# PCB_PressureSensitiveConverterBoard.net
KiCad netlist of a schematic drawn in EasyEDA Pro
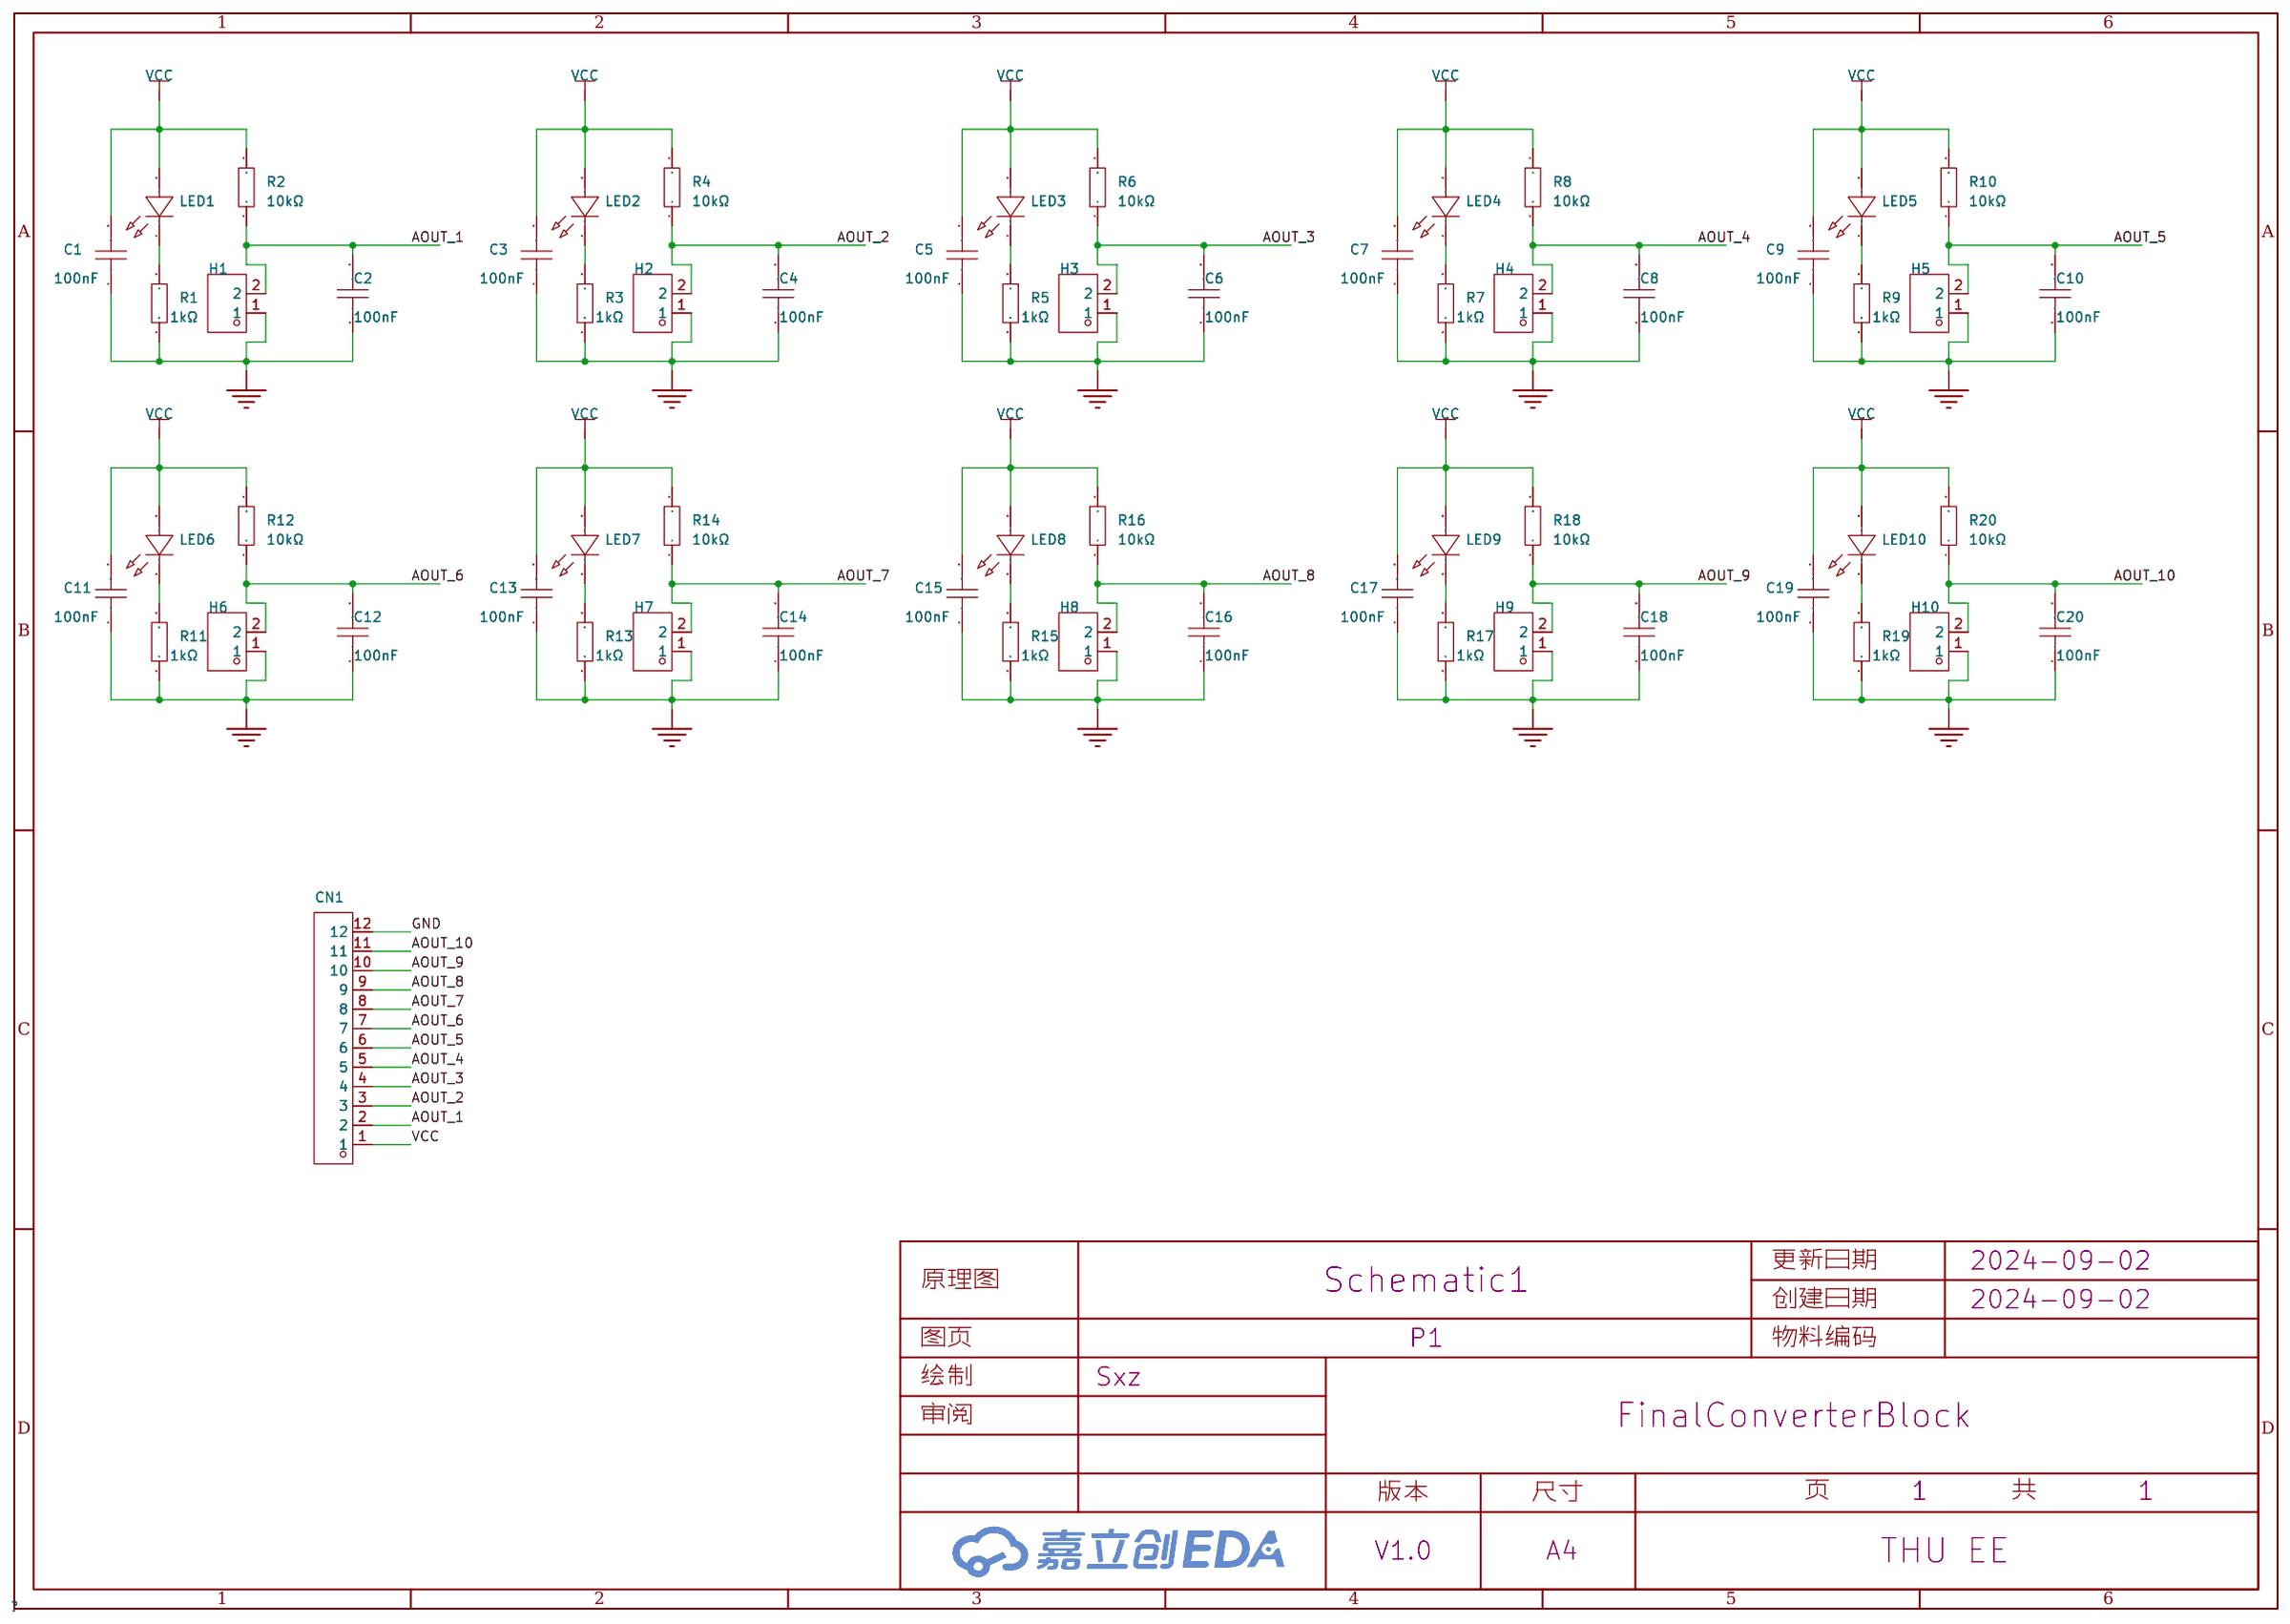
[diagram p0: schematic sheet]

(export (version "E")
  (design (tool "Eeschema 10.0.6"))
  (components
    (comp (ref "C1")
      (value "100nF")
      (footprint "easyedapro:C0603")
      (description "容值:100nF;精度:±10%;额定电压:50V;材质(温度系数):X7R;")
      (fields
        (field (name "Manufacturer Part") "CC0603KRX7R9BB104")
        (field (name "Manufacturer") "YAGEO(国巨)")
      )
      (libsource (lib "easyedapro") (part "CC0603KRX7R9BB104"))
    )
    (comp (ref "C2")
      (value "100nF")
      (footprint "easyedapro:C0603")
      (description "容值:100nF;精度:±10%;额定电压:50V;材质(温度系数):X7R;")
      (fields
        (field (name "Manufacturer Part") "CC0603KRX7R9BB104")
        (field (name "Manufacturer") "YAGEO(国巨)")
      )
      (libsource (lib "easyedapro") (part "CC0603KRX7R9BB104"))
    )
    (comp (ref "C3")
      (value "100nF")
      (footprint "easyedapro:C0603")
      (description "容值:100nF;精度:±10%;额定电压:50V;材质(温度系数):X7R;")
      (fields
        (field (name "Manufacturer Part") "CC0603KRX7R9BB104")
        (field (name "Manufacturer") "YAGEO(国巨)")
      )
      (libsource (lib "easyedapro") (part "CC0603KRX7R9BB104"))
    )
    (comp (ref "C4")
      (value "100nF")
      (footprint "easyedapro:C0603")
      (description "容值:100nF;精度:±10%;额定电压:50V;材质(温度系数):X7R;")
      (fields
        (field (name "Manufacturer Part") "CC0603KRX7R9BB104")
        (field (name "Manufacturer") "YAGEO(国巨)")
      )
      (libsource (lib "easyedapro") (part "CC0603KRX7R9BB104"))
    )
    (comp (ref "C5")
      (value "100nF")
      (footprint "easyedapro:C0603")
      (description "容值:100nF;精度:±10%;额定电压:50V;材质(温度系数):X7R;")
      (fields
        (field (name "Manufacturer Part") "CC0603KRX7R9BB104")
        (field (name "Manufacturer") "YAGEO(国巨)")
      )
      (libsource (lib "easyedapro") (part "CC0603KRX7R9BB104"))
    )
    (comp (ref "C6")
      (value "100nF")
      (footprint "easyedapro:C0603")
      (description "容值:100nF;精度:±10%;额定电压:50V;材质(温度系数):X7R;")
      (fields
        (field (name "Manufacturer Part") "CC0603KRX7R9BB104")
        (field (name "Manufacturer") "YAGEO(国巨)")
      )
      (libsource (lib "easyedapro") (part "CC0603KRX7R9BB104"))
    )
    (comp (ref "C7")
      (value "100nF")
      (footprint "easyedapro:C0603")
      (description "容值:100nF;精度:±10%;额定电压:50V;材质(温度系数):X7R;")
      (fields
        (field (name "Manufacturer Part") "CC0603KRX7R9BB104")
        (field (name "Manufacturer") "YAGEO(国巨)")
      )
      (libsource (lib "easyedapro") (part "CC0603KRX7R9BB104"))
    )
    (comp (ref "C8")
      (value "100nF")
      (footprint "easyedapro:C0603")
      (description "容值:100nF;精度:±10%;额定电压:50V;材质(温度系数):X7R;")
      (fields
        (field (name "Manufacturer Part") "CC0603KRX7R9BB104")
        (field (name "Manufacturer") "YAGEO(国巨)")
      )
      (libsource (lib "easyedapro") (part "CC0603KRX7R9BB104"))
    )
    (comp (ref "C9")
      (value "100nF")
      (footprint "easyedapro:C0603")
      (description "容值:100nF;精度:±10%;额定电压:50V;材质(温度系数):X7R;")
      (fields
        (field (name "Manufacturer Part") "CC0603KRX7R9BB104")
        (field (name "Manufacturer") "YAGEO(国巨)")
      )
      (libsource (lib "easyedapro") (part "CC0603KRX7R9BB104"))
    )
    (comp (ref "C10")
      (value "100nF")
      (footprint "easyedapro:C0603")
      (description "容值:100nF;精度:±10%;额定电压:50V;材质(温度系数):X7R;")
      (fields
        (field (name "Manufacturer Part") "CC0603KRX7R9BB104")
        (field (name "Manufacturer") "YAGEO(国巨)")
      )
      (libsource (lib "easyedapro") (part "CC0603KRX7R9BB104"))
    )
    (comp (ref "C11")
      (value "100nF")
      (footprint "easyedapro:C0603")
      (description "容值:100nF;精度:±10%;额定电压:50V;材质(温度系数):X7R;")
      (fields
        (field (name "Manufacturer Part") "CC0603KRX7R9BB104")
        (field (name "Manufacturer") "YAGEO(国巨)")
      )
      (libsource (lib "easyedapro") (part "CC0603KRX7R9BB104"))
    )
    (comp (ref "C12")
      (value "100nF")
      (footprint "easyedapro:C0603")
      (description "容值:100nF;精度:±10%;额定电压:50V;材质(温度系数):X7R;")
      (fields
        (field (name "Manufacturer Part") "CC0603KRX7R9BB104")
        (field (name "Manufacturer") "YAGEO(国巨)")
      )
      (libsource (lib "easyedapro") (part "CC0603KRX7R9BB104"))
    )
    (comp (ref "C13")
      (value "100nF")
      (footprint "easyedapro:C0603")
      (description "容值:100nF;精度:±10%;额定电压:50V;材质(温度系数):X7R;")
      (fields
        (field (name "Manufacturer Part") "CC0603KRX7R9BB104")
        (field (name "Manufacturer") "YAGEO(国巨)")
      )
      (libsource (lib "easyedapro") (part "CC0603KRX7R9BB104"))
    )
    (comp (ref "C14")
      (value "100nF")
      (footprint "easyedapro:C0603")
      (description "容值:100nF;精度:±10%;额定电压:50V;材质(温度系数):X7R;")
      (fields
        (field (name "Manufacturer Part") "CC0603KRX7R9BB104")
        (field (name "Manufacturer") "YAGEO(国巨)")
      )
      (libsource (lib "easyedapro") (part "CC0603KRX7R9BB104"))
    )
    (comp (ref "C15")
      (value "100nF")
      (footprint "easyedapro:C0603")
      (description "容值:100nF;精度:±10%;额定电压:50V;材质(温度系数):X7R;")
      (fields
        (field (name "Manufacturer Part") "CC0603KRX7R9BB104")
        (field (name "Manufacturer") "YAGEO(国巨)")
      )
      (libsource (lib "easyedapro") (part "CC0603KRX7R9BB104"))
    )
    (comp (ref "C16")
      (value "100nF")
      (footprint "easyedapro:C0603")
      (description "容值:100nF;精度:±10%;额定电压:50V;材质(温度系数):X7R;")
      (fields
        (field (name "Manufacturer Part") "CC0603KRX7R9BB104")
        (field (name "Manufacturer") "YAGEO(国巨)")
      )
      (libsource (lib "easyedapro") (part "CC0603KRX7R9BB104"))
    )
    (comp (ref "C17")
      (value "100nF")
      (footprint "easyedapro:C0603")
      (description "容值:100nF;精度:±10%;额定电压:50V;材质(温度系数):X7R;")
      (fields
        (field (name "Manufacturer Part") "CC0603KRX7R9BB104")
        (field (name "Manufacturer") "YAGEO(国巨)")
      )
      (libsource (lib "easyedapro") (part "CC0603KRX7R9BB104"))
    )
    (comp (ref "C18")
      (value "100nF")
      (footprint "easyedapro:C0603")
      (description "容值:100nF;精度:±10%;额定电压:50V;材质(温度系数):X7R;")
      (fields
        (field (name "Manufacturer Part") "CC0603KRX7R9BB104")
        (field (name "Manufacturer") "YAGEO(国巨)")
      )
      (libsource (lib "easyedapro") (part "CC0603KRX7R9BB104"))
    )
    (comp (ref "C19")
      (value "100nF")
      (footprint "easyedapro:C0603")
      (description "容值:100nF;精度:±10%;额定电压:50V;材质(温度系数):X7R;")
      (fields
        (field (name "Manufacturer Part") "CC0603KRX7R9BB104")
        (field (name "Manufacturer") "YAGEO(国巨)")
      )
      (libsource (lib "easyedapro") (part "CC0603KRX7R9BB104"))
    )
    (comp (ref "C20")
      (value "100nF")
      (footprint "easyedapro:C0603")
      (description "容值:100nF;精度:±10%;额定电压:50V;材质(温度系数):X7R;")
      (fields
        (field (name "Manufacturer Part") "CC0603KRX7R9BB104")
        (field (name "Manufacturer") "YAGEO(国巨)")
      )
      (libsource (lib "easyedapro") (part "CC0603KRX7R9BB104"))
    )
    (comp (ref "CN1")
      (value "HB-PH3-254112PB2GOP")
      (footprint "easyedapro:HDR-TH_12P-P2.54-V-M")
      (fields (field (name "Manufacturer") "HANBO(汉博)"))
      (libsource (lib "easyedapro") (part "HB-PH3-254112PB2GOP"))
    )
    (comp (ref "H1")
      (value "PZ254V-11-02P")
      (footprint "easyedapro:HDR-TH_2P-P2.54-V-M")
      (fields (field (name "Manufacturer") "XFCN(兴飞)"))
      (libsource (lib "easyedapro") (part "PZ254V-11-02P"))
    )
    (comp (ref "H2")
      (value "PZ254V-11-02P")
      (footprint "easyedapro:HDR-TH_2P-P2.54-V-M")
      (fields (field (name "Manufacturer") "XFCN(兴飞)"))
      (libsource (lib "easyedapro") (part "PZ254V-11-02P"))
    )
    (comp (ref "H3")
      (value "PZ254V-11-02P")
      (footprint "easyedapro:HDR-TH_2P-P2.54-V-M")
      (fields (field (name "Manufacturer") "XFCN(兴飞)"))
      (libsource (lib "easyedapro") (part "PZ254V-11-02P"))
    )
    (comp (ref "H4")
      (value "PZ254V-11-02P")
      (footprint "easyedapro:HDR-TH_2P-P2.54-V-M")
      (fields (field (name "Manufacturer") "XFCN(兴飞)"))
      (libsource (lib "easyedapro") (part "PZ254V-11-02P"))
    )
    (comp (ref "H5")
      (value "PZ254V-11-02P")
      (footprint "easyedapro:HDR-TH_2P-P2.54-V-M")
      (fields (field (name "Manufacturer") "XFCN(兴飞)"))
      (libsource (lib "easyedapro") (part "PZ254V-11-02P"))
    )
    (comp (ref "H6")
      (value "PZ254V-11-02P")
      (footprint "easyedapro:HDR-TH_2P-P2.54-V-M")
      (fields (field (name "Manufacturer") "XFCN(兴飞)"))
      (libsource (lib "easyedapro") (part "PZ254V-11-02P"))
    )
    (comp (ref "H7")
      (value "PZ254V-11-02P")
      (footprint "easyedapro:HDR-TH_2P-P2.54-V-M")
      (fields (field (name "Manufacturer") "XFCN(兴飞)"))
      (libsource (lib "easyedapro") (part "PZ254V-11-02P"))
    )
    (comp (ref "H8")
      (value "PZ254V-11-02P")
      (footprint "easyedapro:HDR-TH_2P-P2.54-V-M")
      (fields (field (name "Manufacturer") "XFCN(兴飞)"))
      (libsource (lib "easyedapro") (part "PZ254V-11-02P"))
    )
    (comp (ref "H9")
      (value "PZ254V-11-02P")
      (footprint "easyedapro:HDR-TH_2P-P2.54-V-M")
      (fields (field (name "Manufacturer") "XFCN(兴飞)"))
      (libsource (lib "easyedapro") (part "PZ254V-11-02P"))
    )
    (comp (ref "H10")
      (value "PZ254V-11-02P")
      (footprint "easyedapro:HDR-TH_2P-P2.54-V-M")
      (fields (field (name "Manufacturer") "XFCN(兴飞)"))
      (libsource (lib "easyedapro") (part "PZ254V-11-02P"))
    )
    (comp (ref "LED1")
      (value "XL-1608SURC-06")
      (footprint "easyedapro:LED0603-RD_RED")
      (description "发光颜色:红色;功率:55mW;正向电流:25mA;主波长:617nm~621nm;透镜颜色:无色透明透镜;色温:-;发光角度:120°;载带方式:正贴;工作温度:-30°C~+85°C;")
      (fields (field (name "Manufacturer") "XINGLIGHT(成兴光)"))
      (libsource (lib "easyedapro") (part "XL-1608SURC-06"))
    )
    (comp (ref "LED2")
      (value "XL-1608SURC-06")
      (footprint "easyedapro:LED0603-RD_RED")
      (description "发光颜色:红色;功率:55mW;正向电流:25mA;主波长:617nm~621nm;透镜颜色:无色透明透镜;色温:-;发光角度:120°;载带方式:正贴;工作温度:-30°C~+85°C;")
      (fields (field (name "Manufacturer") "XINGLIGHT(成兴光)"))
      (libsource (lib "easyedapro") (part "XL-1608SURC-06"))
    )
    (comp (ref "LED3")
      (value "XL-1608SURC-06")
      (footprint "easyedapro:LED0603-RD_RED")
      (description "发光颜色:红色;功率:55mW;正向电流:25mA;主波长:617nm~621nm;透镜颜色:无色透明透镜;色温:-;发光角度:120°;载带方式:正贴;工作温度:-30°C~+85°C;")
      (fields (field (name "Manufacturer") "XINGLIGHT(成兴光)"))
      (libsource (lib "easyedapro") (part "XL-1608SURC-06"))
    )
    (comp (ref "LED4")
      (value "XL-1608SURC-06")
      (footprint "easyedapro:LED0603-RD_RED")
      (description "发光颜色:红色;功率:55mW;正向电流:25mA;主波长:617nm~621nm;透镜颜色:无色透明透镜;色温:-;发光角度:120°;载带方式:正贴;工作温度:-30°C~+85°C;")
      (fields (field (name "Manufacturer") "XINGLIGHT(成兴光)"))
      (libsource (lib "easyedapro") (part "XL-1608SURC-06"))
    )
    (comp (ref "LED5")
      (value "XL-1608SURC-06")
      (footprint "easyedapro:LED0603-RD_RED")
      (description "发光颜色:红色;功率:55mW;正向电流:25mA;主波长:617nm~621nm;透镜颜色:无色透明透镜;色温:-;发光角度:120°;载带方式:正贴;工作温度:-30°C~+85°C;")
      (fields (field (name "Manufacturer") "XINGLIGHT(成兴光)"))
      (libsource (lib "easyedapro") (part "XL-1608SURC-06"))
    )
    (comp (ref "LED6")
      (value "XL-1608SURC-06")
      (footprint "easyedapro:LED0603-RD_RED")
      (description "发光颜色:红色;功率:55mW;正向电流:25mA;主波长:617nm~621nm;透镜颜色:无色透明透镜;色温:-;发光角度:120°;载带方式:正贴;工作温度:-30°C~+85°C;")
      (fields (field (name "Manufacturer") "XINGLIGHT(成兴光)"))
      (libsource (lib "easyedapro") (part "XL-1608SURC-06"))
    )
    (comp (ref "LED7")
      (value "XL-1608SURC-06")
      (footprint "easyedapro:LED0603-RD_RED")
      (description "发光颜色:红色;功率:55mW;正向电流:25mA;主波长:617nm~621nm;透镜颜色:无色透明透镜;色温:-;发光角度:120°;载带方式:正贴;工作温度:-30°C~+85°C;")
      (fields (field (name "Manufacturer") "XINGLIGHT(成兴光)"))
      (libsource (lib "easyedapro") (part "XL-1608SURC-06"))
    )
    (comp (ref "LED8")
      (value "XL-1608SURC-06")
      (footprint "easyedapro:LED0603-RD_RED")
      (description "发光颜色:红色;功率:55mW;正向电流:25mA;主波长:617nm~621nm;透镜颜色:无色透明透镜;色温:-;发光角度:120°;载带方式:正贴;工作温度:-30°C~+85°C;")
      (fields (field (name "Manufacturer") "XINGLIGHT(成兴光)"))
      (libsource (lib "easyedapro") (part "XL-1608SURC-06"))
    )
    (comp (ref "LED9")
      (value "XL-1608SURC-06")
      (footprint "easyedapro:LED0603-RD_RED")
      (description "发光颜色:红色;功率:55mW;正向电流:25mA;主波长:617nm~621nm;透镜颜色:无色透明透镜;色温:-;发光角度:120°;载带方式:正贴;工作温度:-30°C~+85°C;")
      (fields (field (name "Manufacturer") "XINGLIGHT(成兴光)"))
      (libsource (lib "easyedapro") (part "XL-1608SURC-06"))
    )
    (comp (ref "LED10")
      (value "XL-1608SURC-06")
      (footprint "easyedapro:LED0603-RD_RED")
      (description "发光颜色:红色;功率:55mW;正向电流:25mA;主波长:617nm~621nm;透镜颜色:无色透明透镜;色温:-;发光角度:120°;载带方式:正贴;工作温度:-30°C~+85°C;")
      (fields (field (name "Manufacturer") "XINGLIGHT(成兴光)"))
      (libsource (lib "easyedapro") (part "XL-1608SURC-06"))
    )
    (comp (ref "R1")
      (value "1kΩ")
      (footprint "easyedapro:R0603")
      (description "电阻类型:厚膜电阻;阻值:1kΩ;精度:±1%;功率:100mW;最大工作电压:75V;温度系数:±100ppm/°C;")
      (fields
        (field (name "Manufacturer Part") "0603WAF1001T5E")
        (field (name "Manufacturer") "UNI-ROYAL(厚声)")
      )
      (libsource (lib "easyedapro") (part "0603WAF1001T5E"))
    )
    (comp (ref "R2")
      (value "10kΩ")
      (footprint "easyedapro:R0603")
      (description "电阻类型:厚膜电阻;阻值:10kΩ;精度:±1%;功率:100mW;最大工作电压:75V;温度系数:±100ppm/°C;")
      (fields
        (field (name "Manufacturer Part") "0603WAF1002T5E")
        (field (name "Manufacturer") "UNI-ROYAL(厚声)")
      )
      (libsource (lib "easyedapro") (part "0603WAF1002T5E"))
    )
    (comp (ref "R3")
      (value "1kΩ")
      (footprint "easyedapro:R0603")
      (description "电阻类型:厚膜电阻;阻值:1kΩ;精度:±1%;功率:100mW;最大工作电压:75V;温度系数:±100ppm/°C;")
      (fields
        (field (name "Manufacturer Part") "0603WAF1001T5E")
        (field (name "Manufacturer") "UNI-ROYAL(厚声)")
      )
      (libsource (lib "easyedapro") (part "0603WAF1001T5E"))
    )
    (comp (ref "R4")
      (value "10kΩ")
      (footprint "easyedapro:R0603")
      (description "电阻类型:厚膜电阻;阻值:10kΩ;精度:±1%;功率:100mW;最大工作电压:75V;温度系数:±100ppm/°C;")
      (fields
        (field (name "Manufacturer Part") "0603WAF1002T5E")
        (field (name "Manufacturer") "UNI-ROYAL(厚声)")
      )
      (libsource (lib "easyedapro") (part "0603WAF1002T5E"))
    )
    (comp (ref "R5")
      (value "1kΩ")
      (footprint "easyedapro:R0603")
      (description "电阻类型:厚膜电阻;阻值:1kΩ;精度:±1%;功率:100mW;最大工作电压:75V;温度系数:±100ppm/°C;")
      (fields
        (field (name "Manufacturer Part") "0603WAF1001T5E")
        (field (name "Manufacturer") "UNI-ROYAL(厚声)")
      )
      (libsource (lib "easyedapro") (part "0603WAF1001T5E"))
    )
    (comp (ref "R6")
      (value "10kΩ")
      (footprint "easyedapro:R0603")
      (description "电阻类型:厚膜电阻;阻值:10kΩ;精度:±1%;功率:100mW;最大工作电压:75V;温度系数:±100ppm/°C;")
      (fields
        (field (name "Manufacturer Part") "0603WAF1002T5E")
        (field (name "Manufacturer") "UNI-ROYAL(厚声)")
      )
      (libsource (lib "easyedapro") (part "0603WAF1002T5E"))
    )
    (comp (ref "R7")
      (value "1kΩ")
      (footprint "easyedapro:R0603")
      (description "电阻类型:厚膜电阻;阻值:1kΩ;精度:±1%;功率:100mW;最大工作电压:75V;温度系数:±100ppm/°C;")
      (fields
        (field (name "Manufacturer Part") "0603WAF1001T5E")
        (field (name "Manufacturer") "UNI-ROYAL(厚声)")
      )
      (libsource (lib "easyedapro") (part "0603WAF1001T5E"))
    )
    (comp (ref "R8")
      (value "10kΩ")
      (footprint "easyedapro:R0603")
      (description "电阻类型:厚膜电阻;阻值:10kΩ;精度:±1%;功率:100mW;最大工作电压:75V;温度系数:±100ppm/°C;")
      (fields
        (field (name "Manufacturer Part") "0603WAF1002T5E")
        (field (name "Manufacturer") "UNI-ROYAL(厚声)")
      )
      (libsource (lib "easyedapro") (part "0603WAF1002T5E"))
    )
    (comp (ref "R9")
      (value "1kΩ")
      (footprint "easyedapro:R0603")
      (description "电阻类型:厚膜电阻;阻值:1kΩ;精度:±1%;功率:100mW;最大工作电压:75V;温度系数:±100ppm/°C;")
      (fields
        (field (name "Manufacturer Part") "0603WAF1001T5E")
        (field (name "Manufacturer") "UNI-ROYAL(厚声)")
      )
      (libsource (lib "easyedapro") (part "0603WAF1001T5E"))
    )
    (comp (ref "R10")
      (value "10kΩ")
      (footprint "easyedapro:R0603")
      (description "电阻类型:厚膜电阻;阻值:10kΩ;精度:±1%;功率:100mW;最大工作电压:75V;温度系数:±100ppm/°C;")
      (fields
        (field (name "Manufacturer Part") "0603WAF1002T5E")
        (field (name "Manufacturer") "UNI-ROYAL(厚声)")
      )
      (libsource (lib "easyedapro") (part "0603WAF1002T5E"))
    )
    (comp (ref "R11")
      (value "1kΩ")
      (footprint "easyedapro:R0603")
      (description "电阻类型:厚膜电阻;阻值:1kΩ;精度:±1%;功率:100mW;最大工作电压:75V;温度系数:±100ppm/°C;")
      (fields
        (field (name "Manufacturer Part") "0603WAF1001T5E")
        (field (name "Manufacturer") "UNI-ROYAL(厚声)")
      )
      (libsource (lib "easyedapro") (part "0603WAF1001T5E"))
    )
    (comp (ref "R12")
      (value "10kΩ")
      (footprint "easyedapro:R0603")
      (description "电阻类型:厚膜电阻;阻值:10kΩ;精度:±1%;功率:100mW;最大工作电压:75V;温度系数:±100ppm/°C;")
      (fields
        (field (name "Manufacturer Part") "0603WAF1002T5E")
        (field (name "Manufacturer") "UNI-ROYAL(厚声)")
      )
      (libsource (lib "easyedapro") (part "0603WAF1002T5E"))
    )
    (comp (ref "R13")
      (value "1kΩ")
      (footprint "easyedapro:R0603")
      (description "电阻类型:厚膜电阻;阻值:1kΩ;精度:±1%;功率:100mW;最大工作电压:75V;温度系数:±100ppm/°C;")
      (fields
        (field (name "Manufacturer Part") "0603WAF1001T5E")
        (field (name "Manufacturer") "UNI-ROYAL(厚声)")
      )
      (libsource (lib "easyedapro") (part "0603WAF1001T5E"))
    )
    (comp (ref "R14")
      (value "10kΩ")
      (footprint "easyedapro:R0603")
      (description "电阻类型:厚膜电阻;阻值:10kΩ;精度:±1%;功率:100mW;最大工作电压:75V;温度系数:±100ppm/°C;")
      (fields
        (field (name "Manufacturer Part") "0603WAF1002T5E")
        (field (name "Manufacturer") "UNI-ROYAL(厚声)")
      )
      (libsource (lib "easyedapro") (part "0603WAF1002T5E"))
    )
    (comp (ref "R15")
      (value "1kΩ")
      (footprint "easyedapro:R0603")
      (description "电阻类型:厚膜电阻;阻值:1kΩ;精度:±1%;功率:100mW;最大工作电压:75V;温度系数:±100ppm/°C;")
      (fields
        (field (name "Manufacturer Part") "0603WAF1001T5E")
        (field (name "Manufacturer") "UNI-ROYAL(厚声)")
      )
      (libsource (lib "easyedapro") (part "0603WAF1001T5E"))
    )
    (comp (ref "R16")
      (value "10kΩ")
      (footprint "easyedapro:R0603")
      (description "电阻类型:厚膜电阻;阻值:10kΩ;精度:±1%;功率:100mW;最大工作电压:75V;温度系数:±100ppm/°C;")
      (fields
        (field (name "Manufacturer Part") "0603WAF1002T5E")
        (field (name "Manufacturer") "UNI-ROYAL(厚声)")
      )
      (libsource (lib "easyedapro") (part "0603WAF1002T5E"))
    )
    (comp (ref "R17")
      (value "1kΩ")
      (footprint "easyedapro:R0603")
      (description "电阻类型:厚膜电阻;阻值:1kΩ;精度:±1%;功率:100mW;最大工作电压:75V;温度系数:±100ppm/°C;")
      (fields
        (field (name "Manufacturer Part") "0603WAF1001T5E")
        (field (name "Manufacturer") "UNI-ROYAL(厚声)")
      )
      (libsource (lib "easyedapro") (part "0603WAF1001T5E"))
    )
    (comp (ref "R18")
      (value "10kΩ")
      (footprint "easyedapro:R0603")
      (description "电阻类型:厚膜电阻;阻值:10kΩ;精度:±1%;功率:100mW;最大工作电压:75V;温度系数:±100ppm/°C;")
      (fields
        (field (name "Manufacturer Part") "0603WAF1002T5E")
        (field (name "Manufacturer") "UNI-ROYAL(厚声)")
      )
      (libsource (lib "easyedapro") (part "0603WAF1002T5E"))
    )
    (comp (ref "R19")
      (value "1kΩ")
      (footprint "easyedapro:R0603")
      (description "电阻类型:厚膜电阻;阻值:1kΩ;精度:±1%;功率:100mW;最大工作电压:75V;温度系数:±100ppm/°C;")
      (fields
        (field (name "Manufacturer Part") "0603WAF1001T5E")
        (field (name "Manufacturer") "UNI-ROYAL(厚声)")
      )
      (libsource (lib "easyedapro") (part "0603WAF1001T5E"))
    )
    (comp (ref "R20")
      (value "10kΩ")
      (footprint "easyedapro:R0603")
      (description "电阻类型:厚膜电阻;阻值:10kΩ;精度:±1%;功率:100mW;最大工作电压:75V;温度系数:±100ppm/°C;")
      (fields
        (field (name "Manufacturer Part") "0603WAF1002T5E")
        (field (name "Manufacturer") "UNI-ROYAL(厚声)")
      )
      (libsource (lib "easyedapro") (part "0603WAF1002T5E"))
    )
  )
  (nets
    (net (code "1") (name "/AOUT_1") (class "Default")
      (node (ref "C2") (pin "2") (pinfunction "2_2") (pintype "unspecified"))
      (node (ref "CN1") (pin "2") (pinfunction "2_2") (pintype "unspecified"))
      (node (ref "H1") (pin "2") (pinfunction "2_2") (pintype "unspecified"))
      (node (ref "R2") (pin "1") (pinfunction "1_1") (pintype "input"))
    )
    (net (code "2") (name "/AOUT_2") (class "Default")
      (node (ref "C4") (pin "2") (pinfunction "2_2") (pintype "unspecified"))
      (node (ref "CN1") (pin "3") (pinfunction "3_3") (pintype "unspecified"))
      (node (ref "H2") (pin "2") (pinfunction "2_2") (pintype "unspecified"))
      (node (ref "R4") (pin "1") (pinfunction "1_1") (pintype "input"))
    )
    (net (code "3") (name "/AOUT_3") (class "Default")
      (node (ref "C6") (pin "2") (pinfunction "2_2") (pintype "unspecified"))
      (node (ref "CN1") (pin "4") (pinfunction "4_4") (pintype "unspecified"))
      (node (ref "H3") (pin "2") (pinfunction "2_2") (pintype "unspecified"))
      (node (ref "R6") (pin "1") (pinfunction "1_1") (pintype "input"))
    )
    (net (code "4") (name "/AOUT_4") (class "Default")
      (node (ref "C8") (pin "2") (pinfunction "2_2") (pintype "unspecified"))
      (node (ref "CN1") (pin "5") (pinfunction "5_5") (pintype "unspecified"))
      (node (ref "H4") (pin "2") (pinfunction "2_2") (pintype "unspecified"))
      (node (ref "R8") (pin "1") (pinfunction "1_1") (pintype "input"))
    )
    (net (code "5") (name "/AOUT_5") (class "Default")
      (node (ref "C10") (pin "2") (pinfunction "2_2") (pintype "unspecified"))
      (node (ref "CN1") (pin "6") (pinfunction "6_6") (pintype "unspecified"))
      (node (ref "H5") (pin "2") (pinfunction "2_2") (pintype "unspecified"))
      (node (ref "R10") (pin "1") (pinfunction "1_1") (pintype "input"))
    )
    (net (code "6") (name "/AOUT_6") (class "Default")
      (node (ref "C12") (pin "2") (pinfunction "2_2") (pintype "unspecified"))
      (node (ref "CN1") (pin "7") (pinfunction "7_7") (pintype "unspecified"))
      (node (ref "H6") (pin "2") (pinfunction "2_2") (pintype "unspecified"))
      (node (ref "R12") (pin "1") (pinfunction "1_1") (pintype "input"))
    )
    (net (code "7") (name "/AOUT_7") (class "Default")
      (node (ref "C14") (pin "2") (pinfunction "2_2") (pintype "unspecified"))
      (node (ref "CN1") (pin "8") (pinfunction "8_8") (pintype "unspecified"))
      (node (ref "H7") (pin "2") (pinfunction "2_2") (pintype "unspecified"))
      (node (ref "R14") (pin "1") (pinfunction "1_1") (pintype "input"))
    )
    (net (code "8") (name "/AOUT_8") (class "Default")
      (node (ref "C16") (pin "2") (pinfunction "2_2") (pintype "unspecified"))
      (node (ref "CN1") (pin "9") (pinfunction "9_9") (pintype "unspecified"))
      (node (ref "H8") (pin "2") (pinfunction "2_2") (pintype "unspecified"))
      (node (ref "R16") (pin "1") (pinfunction "1_1") (pintype "input"))
    )
    (net (code "9") (name "/AOUT_9") (class "Default")
      (node (ref "C18") (pin "2") (pinfunction "2_2") (pintype "unspecified"))
      (node (ref "CN1") (pin "10") (pinfunction "10_10") (pintype "unspecified"))
      (node (ref "H9") (pin "2") (pinfunction "2_2") (pintype "unspecified"))
      (node (ref "R18") (pin "1") (pinfunction "1_1") (pintype "input"))
    )
    (net (code "10") (name "/AOUT_10") (class "Default")
      (node (ref "C20") (pin "2") (pinfunction "2_2") (pintype "unspecified"))
      (node (ref "CN1") (pin "11") (pinfunction "11_11") (pintype "unspecified"))
      (node (ref "H10") (pin "2") (pinfunction "2_2") (pintype "unspecified"))
      (node (ref "R20") (pin "1") (pinfunction "1_1") (pintype "input"))
    )
    (net (code "11") (name "GND") (class "Default")
      (node (ref "C1") (pin "1") (pinfunction "1_1") (pintype "unspecified"))
      (node (ref "C10") (pin "1") (pinfunction "1_1") (pintype "unspecified"))
      (node (ref "C11") (pin "1") (pinfunction "1_1") (pintype "unspecified"))
      (node (ref "C12") (pin "1") (pinfunction "1_1") (pintype "unspecified"))
      (node (ref "C13") (pin "1") (pinfunction "1_1") (pintype "unspecified"))
      (node (ref "C14") (pin "1") (pinfunction "1_1") (pintype "unspecified"))
      (node (ref "C15") (pin "1") (pinfunction "1_1") (pintype "unspecified"))
      (node (ref "C16") (pin "1") (pinfunction "1_1") (pintype "unspecified"))
      (node (ref "C17") (pin "1") (pinfunction "1_1") (pintype "unspecified"))
      (node (ref "C18") (pin "1") (pinfunction "1_1") (pintype "unspecified"))
      (node (ref "C19") (pin "1") (pinfunction "1_1") (pintype "unspecified"))
      (node (ref "C2") (pin "1") (pinfunction "1_1") (pintype "unspecified"))
      (node (ref "C20") (pin "1") (pinfunction "1_1") (pintype "unspecified"))
      (node (ref "C3") (pin "1") (pinfunction "1_1") (pintype "unspecified"))
      (node (ref "C4") (pin "1") (pinfunction "1_1") (pintype "unspecified"))
      (node (ref "C5") (pin "1") (pinfunction "1_1") (pintype "unspecified"))
      (node (ref "C6") (pin "1") (pinfunction "1_1") (pintype "unspecified"))
      (node (ref "C7") (pin "1") (pinfunction "1_1") (pintype "unspecified"))
      (node (ref "C8") (pin "1") (pinfunction "1_1") (pintype "unspecified"))
      (node (ref "C9") (pin "1") (pinfunction "1_1") (pintype "unspecified"))
      (node (ref "CN1") (pin "12") (pinfunction "12_12") (pintype "unspecified"))
      (node (ref "H1") (pin "1") (pinfunction "1_1") (pintype "unspecified"))
      (node (ref "H10") (pin "1") (pinfunction "1_1") (pintype "unspecified"))
      (node (ref "H2") (pin "1") (pinfunction "1_1") (pintype "unspecified"))
      (node (ref "H3") (pin "1") (pinfunction "1_1") (pintype "unspecified"))
      (node (ref "H4") (pin "1") (pinfunction "1_1") (pintype "unspecified"))
      (node (ref "H5") (pin "1") (pinfunction "1_1") (pintype "unspecified"))
      (node (ref "H6") (pin "1") (pinfunction "1_1") (pintype "unspecified"))
      (node (ref "H7") (pin "1") (pinfunction "1_1") (pintype "unspecified"))
      (node (ref "H8") (pin "1") (pinfunction "1_1") (pintype "unspecified"))
      (node (ref "H9") (pin "1") (pinfunction "1_1") (pintype "unspecified"))
      (node (ref "R1") (pin "1") (pinfunction "1_1") (pintype "input"))
      (node (ref "R11") (pin "1") (pinfunction "1_1") (pintype "input"))
      (node (ref "R13") (pin "1") (pinfunction "1_1") (pintype "input"))
      (node (ref "R15") (pin "1") (pinfunction "1_1") (pintype "input"))
      (node (ref "R17") (pin "1") (pinfunction "1_1") (pintype "input"))
      (node (ref "R19") (pin "1") (pinfunction "1_1") (pintype "input"))
      (node (ref "R3") (pin "1") (pinfunction "1_1") (pintype "input"))
      (node (ref "R5") (pin "1") (pinfunction "1_1") (pintype "input"))
      (node (ref "R7") (pin "1") (pinfunction "1_1") (pintype "input"))
      (node (ref "R9") (pin "1") (pinfunction "1_1") (pintype "input"))
    )
    (net (code "12") (name "Net-(LED1-K)") (class "Default")
      (node (ref "LED1") (pin "1") (pinfunction "K_1") (pintype "unspecified"))
      (node (ref "R1") (pin "2") (pinfunction "2_2") (pintype "input"))
    )
    (net (code "13") (name "Net-(LED2-K)") (class "Default")
      (node (ref "LED2") (pin "1") (pinfunction "K_1") (pintype "unspecified"))
      (node (ref "R3") (pin "2") (pinfunction "2_2") (pintype "input"))
    )
    (net (code "14") (name "Net-(LED3-K)") (class "Default")
      (node (ref "LED3") (pin "1") (pinfunction "K_1") (pintype "unspecified"))
      (node (ref "R5") (pin "2") (pinfunction "2_2") (pintype "input"))
    )
    (net (code "15") (name "Net-(LED4-K)") (class "Default")
      (node (ref "LED4") (pin "1") (pinfunction "K_1") (pintype "unspecified"))
      (node (ref "R7") (pin "2") (pinfunction "2_2") (pintype "input"))
    )
    (net (code "16") (name "Net-(LED5-K)") (class "Default")
      (node (ref "LED5") (pin "1") (pinfunction "K_1") (pintype "unspecified"))
      (node (ref "R9") (pin "2") (pinfunction "2_2") (pintype "input"))
    )
    (net (code "17") (name "Net-(LED6-K)") (class "Default")
      (node (ref "LED6") (pin "1") (pinfunction "K_1") (pintype "unspecified"))
      (node (ref "R11") (pin "2") (pinfunction "2_2") (pintype "input"))
    )
    (net (code "18") (name "Net-(LED7-K)") (class "Default")
      (node (ref "LED7") (pin "1") (pinfunction "K_1") (pintype "unspecified"))
      (node (ref "R13") (pin "2") (pinfunction "2_2") (pintype "input"))
    )
    (net (code "19") (name "Net-(LED8-K)") (class "Default")
      (node (ref "LED8") (pin "1") (pinfunction "K_1") (pintype "unspecified"))
      (node (ref "R15") (pin "2") (pinfunction "2_2") (pintype "input"))
    )
    (net (code "20") (name "Net-(LED9-K)") (class "Default")
      (node (ref "LED9") (pin "1") (pinfunction "K_1") (pintype "unspecified"))
      (node (ref "R17") (pin "2") (pinfunction "2_2") (pintype "input"))
    )
    (net (code "21") (name "Net-(LED10-K)") (class "Default")
      (node (ref "LED10") (pin "1") (pinfunction "K_1") (pintype "unspecified"))
      (node (ref "R19") (pin "2") (pinfunction "2_2") (pintype "input"))
    )
    (net (code "22") (name "VCC") (class "Default")
      (node (ref "C1") (pin "2") (pinfunction "2_2") (pintype "unspecified"))
      (node (ref "C11") (pin "2") (pinfunction "2_2") (pintype "unspecified"))
      (node (ref "C13") (pin "2") (pinfunction "2_2") (pintype "unspecified"))
      (node (ref "C15") (pin "2") (pinfunction "2_2") (pintype "unspecified"))
      (node (ref "C17") (pin "2") (pinfunction "2_2") (pintype "unspecified"))
      (node (ref "C19") (pin "2") (pinfunction "2_2") (pintype "unspecified"))
      (node (ref "C3") (pin "2") (pinfunction "2_2") (pintype "unspecified"))
      (node (ref "C5") (pin "2") (pinfunction "2_2") (pintype "unspecified"))
      (node (ref "C7") (pin "2") (pinfunction "2_2") (pintype "unspecified"))
      (node (ref "C9") (pin "2") (pinfunction "2_2") (pintype "unspecified"))
      (node (ref "CN1") (pin "1") (pinfunction "1_1") (pintype "unspecified"))
      (node (ref "LED1") (pin "2") (pinfunction "A_2") (pintype "unspecified"))
      (node (ref "LED10") (pin "2") (pinfunction "A_2") (pintype "unspecified"))
      (node (ref "LED2") (pin "2") (pinfunction "A_2") (pintype "unspecified"))
      (node (ref "LED3") (pin "2") (pinfunction "A_2") (pintype "unspecified"))
      (node (ref "LED4") (pin "2") (pinfunction "A_2") (pintype "unspecified"))
      (node (ref "LED5") (pin "2") (pinfunction "A_2") (pintype "unspecified"))
      (node (ref "LED6") (pin "2") (pinfunction "A_2") (pintype "unspecified"))
      (node (ref "LED7") (pin "2") (pinfunction "A_2") (pintype "unspecified"))
      (node (ref "LED8") (pin "2") (pinfunction "A_2") (pintype "unspecified"))
      (node (ref "LED9") (pin "2") (pinfunction "A_2") (pintype "unspecified"))
      (node (ref "R10") (pin "2") (pinfunction "2_2") (pintype "input"))
      (node (ref "R12") (pin "2") (pinfunction "2_2") (pintype "input"))
      (node (ref "R14") (pin "2") (pinfunction "2_2") (pintype "input"))
      (node (ref "R16") (pin "2") (pinfunction "2_2") (pintype "input"))
      (node (ref "R18") (pin "2") (pinfunction "2_2") (pintype "input"))
      (node (ref "R2") (pin "2") (pinfunction "2_2") (pintype "input"))
      (node (ref "R20") (pin "2") (pinfunction "2_2") (pintype "input"))
      (node (ref "R4") (pin "2") (pinfunction "2_2") (pintype "input"))
      (node (ref "R6") (pin "2") (pinfunction "2_2") (pintype "input"))
      (node (ref "R8") (pin "2") (pinfunction "2_2") (pintype "input"))
    )
  )
)
